# 1u_panel_breakout.net
KiCad netlist of a schematic drawn in EAGLE
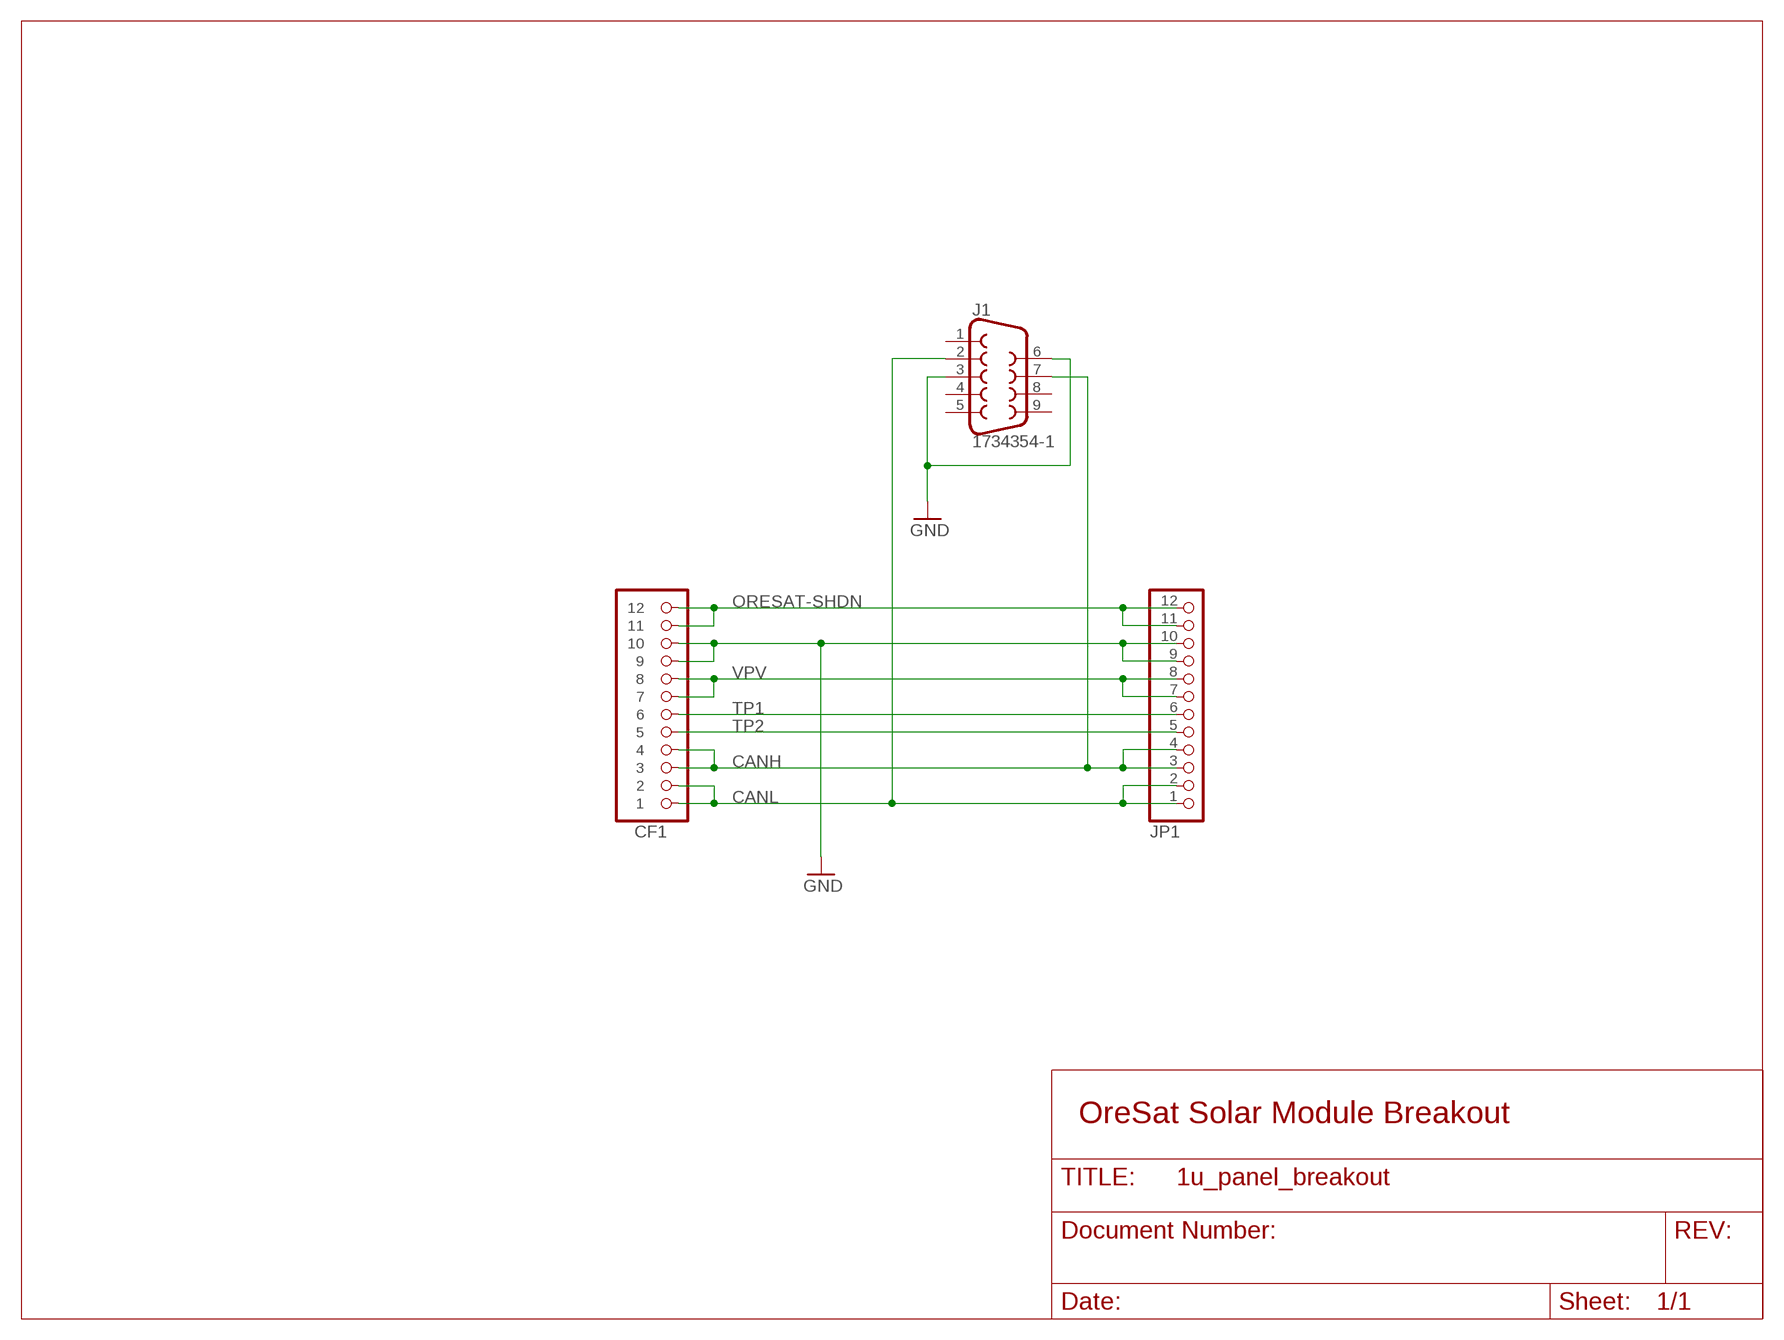
[diagram p0: schematic, sheet 1]

(export (version "E")
  (design (tool "Eeschema 10.0.6"))
  (components
    (comp (ref "CF1")
      (value "ORESAT-SOLARPANEL-12PIN")
      (footprint "eagle-import:CON-1.27-F-HARTING-1522012X601XXX")
      (libsource (lib "eagle-import") (part "ORESAT-SOLARPANEL-12PIN"))
    )
    (comp (ref "J1")
      (value "1734354-1")
      (footprint "eagle-import:TE_1734354-1")
      (libsource (lib "eagle-import") (part "TE_DE9_RECEPTACLE1734354-1"))
    )
    (comp (ref "JP1")
      (value "PINHD-1X12")
      (footprint "eagle-import:1X12")
      (libsource (lib "eagle-import") (part "PINHD-1X12"))
    )
  )
  (nets
    (net (code "1") (name "/CANH") (class "Default")
      (node (ref "CF1") (pin "3") (pinfunction "3_3") (pintype "passive"))
      (node (ref "CF1") (pin "4") (pinfunction "4_4") (pintype "passive"))
      (node (ref "J1") (pin "7") (pinfunction "7_7") (pintype "passive"))
      (node (ref "JP1") (pin "3") (pinfunction "3_3") (pintype "passive"))
      (node (ref "JP1") (pin "4") (pinfunction "4_4") (pintype "passive"))
    )
    (net (code "2") (name "/CANL") (class "Default")
      (node (ref "CF1") (pin "1") (pinfunction "1_1") (pintype "passive"))
      (node (ref "CF1") (pin "2") (pinfunction "2_2") (pintype "passive"))
      (node (ref "J1") (pin "2") (pinfunction "2_2") (pintype "passive"))
      (node (ref "JP1") (pin "1") (pinfunction "1_1") (pintype "passive"))
      (node (ref "JP1") (pin "2") (pinfunction "2_2") (pintype "passive"))
    )
    (net (code "3") (name "/ORESAT-SHDN") (class "Default")
      (node (ref "CF1") (pin "11") (pinfunction "11_11") (pintype "passive"))
      (node (ref "CF1") (pin "12") (pinfunction "12_12") (pintype "passive"))
      (node (ref "JP1") (pin "11") (pinfunction "11_11") (pintype "passive"))
      (node (ref "JP1") (pin "12") (pinfunction "12_12") (pintype "passive"))
    )
    (net (code "4") (name "/TP1") (class "Default")
      (node (ref "CF1") (pin "6") (pinfunction "6_6") (pintype "passive"))
      (node (ref "JP1") (pin "6") (pinfunction "6_6") (pintype "passive"))
    )
    (net (code "5") (name "/TP2") (class "Default")
      (node (ref "CF1") (pin "5") (pinfunction "5_5") (pintype "passive"))
      (node (ref "JP1") (pin "5") (pinfunction "5_5") (pintype "passive"))
    )
    (net (code "6") (name "/VPV") (class "Default")
      (node (ref "CF1") (pin "7") (pinfunction "7_7") (pintype "passive"))
      (node (ref "CF1") (pin "8") (pinfunction "8_8") (pintype "passive"))
      (node (ref "JP1") (pin "7") (pinfunction "7_7") (pintype "passive"))
      (node (ref "JP1") (pin "8") (pinfunction "8_8") (pintype "passive"))
    )
    (net (code "7") (name "GND") (class "Default")
      (node (ref "CF1") (pin "10") (pinfunction "10_10") (pintype "passive"))
      (node (ref "CF1") (pin "9") (pinfunction "9_9") (pintype "passive"))
      (node (ref "J1") (pin "3") (pinfunction "3_3") (pintype "passive"))
      (node (ref "J1") (pin "6") (pinfunction "6_6") (pintype "passive"))
      (node (ref "JP1") (pin "10") (pinfunction "10_10") (pintype "passive"))
      (node (ref "JP1") (pin "9") (pinfunction "9_9") (pintype "passive"))
    )
    (net (code "8") (name "unconnected-(J1-Pad1)") (class "Default")
      (node (ref "J1") (pin "1") (pinfunction "1_1") (pintype "passive"))
    )
    (net (code "9") (name "unconnected-(J1-Pad4)") (class "Default")
      (node (ref "J1") (pin "4") (pinfunction "4_4") (pintype "passive"))
    )
    (net (code "10") (name "unconnected-(J1-Pad5)") (class "Default")
      (node (ref "J1") (pin "5") (pinfunction "5_5") (pintype "passive"))
    )
    (net (code "11") (name "unconnected-(J1-Pad8)") (class "Default")
      (node (ref "J1") (pin "8") (pinfunction "8_8") (pintype "passive"))
    )
    (net (code "12") (name "unconnected-(J1-Pad9)") (class "Default")
      (node (ref "J1") (pin "9") (pinfunction "9_9") (pintype "passive"))
    )
  )
)
